# Top.net
KiCad netlist of a schematic drawn in Altium Designer
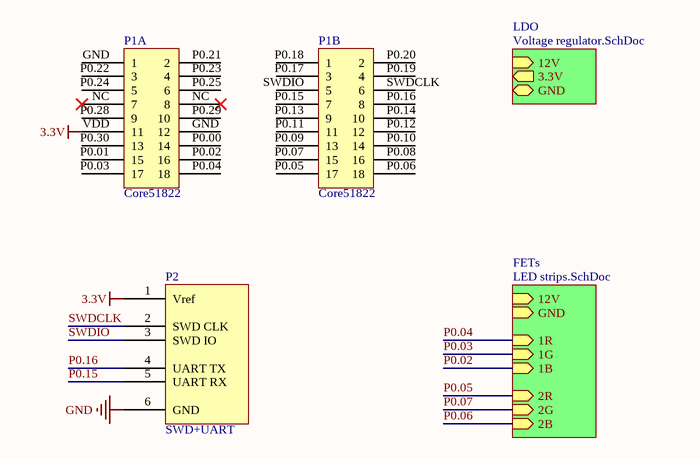
[diagram p0: Top.SchDoc]

(export (version "E")
  (design (tool "Eeschema 10.0.6"))
  (components
    (comp (ref "P1") (value "Core51822") (libsource (lib "Core51822-related") (part "Core51822")))
    (comp (ref "P2") (value "SWD+UART") (libsource (lib "Core51822-related") (part "SWD+UART")))
  )
  (nets
    (net (code "12") (name "/P0.15") (class "Default")
      (node (ref "P2") (pin "5") (pinfunction "UART_RX_5") (pintype "passive"))
    )
    (net (code "13") (name "/P0.16") (class "Default")
      (node (ref "P2") (pin "4") (pinfunction "UART_TX_4") (pintype "passive"))
    )
    (net (code "14") (name "/SWDCLK") (class "Default")
      (node (ref "P2") (pin "2") (pinfunction "SWD_CLK_2") (pintype "passive"))
    )
    (net (code "15") (name "/SWDIO") (class "Default")
      (node (ref "P2") (pin "3") (pinfunction "SWD_IO_3") (pintype "passive"))
    )
    (net (code "16") (name "3.3V") (class "Default")
      (node (ref "P1") (pin "VDD") (pinfunction "11_VDD") (pintype "passive"))
      (node (ref "P2") (pin "1") (pinfunction "Vref_1") (pintype "passive"))
    )
    (net (code "17") (name "GND") (class "Default")
      (node (ref "P2") (pin "6") (pinfunction "GND_6") (pintype "passive"))
    )
    (net (code "18") (name "unconnected-(P1A-1-PadGND)") (class "Default")
      (node (ref "P1") (pin "GND") (pinfunction "1_GND") (pintype "passive"))
    )
    (net (code "19") (name "unconnected-(P1A-2-PadP0.21)") (class "Default")
      (node (ref "P1") (pin "P0.21") (pinfunction "2_P0.21") (pintype "passive"))
    )
    (net (code "20") (name "unconnected-(P1A-3-PadP0.22)") (class "Default")
      (node (ref "P1") (pin "P0.22") (pinfunction "3_P0.22") (pintype "power_in"))
    )
    (net (code "21") (name "unconnected-(P1A-4-PadP0.23)") (class "Default")
      (node (ref "P1") (pin "P0.23") (pinfunction "4_P0.23") (pintype "passive"))
    )
    (net (code "22") (name "unconnected-(P1A-5-PadP0.24)") (class "Default")
      (node (ref "P1") (pin "P0.24") (pinfunction "5_P0.24") (pintype "passive"))
    )
    (net (code "23") (name "unconnected-(P1A-6-PadP0.25)") (class "Default")
      (node (ref "P1") (pin "P0.25") (pinfunction "6_P0.25") (pintype "passive"))
    )
    (net (code "24") (name "unconnected-(P1A-7-PadNC)") (class "Default")
      (node (ref "P1") (pin "NC") (pinfunction "7_NC") (pintype "passive+no_connect"))
    )
    (net (code "25") (name "unconnected-(P1A-8-PadNC)") (class "Default")
      (node (ref "P1") (pin "NC") (pinfunction "8_NC") (pintype "passive+no_connect"))
    )
    (net (code "26") (name "unconnected-(P1A-9-PadP0.28)") (class "Default")
      (node (ref "P1") (pin "P0.28") (pinfunction "9_P0.28") (pintype "passive"))
    )
    (net (code "27") (name "unconnected-(P1A-10-PadP0.29)") (class "Default")
      (node (ref "P1") (pin "P0.29") (pinfunction "10_P0.29") (pintype "passive"))
    )
    (net (code "28") (name "unconnected-(P1A-12-PadGND)") (class "Default")
      (node (ref "P1") (pin "GND") (pinfunction "12_GND") (pintype "passive"))
    )
    (net (code "29") (name "unconnected-(P1A-13-PadP0.30)") (class "Default")
      (node (ref "P1") (pin "P0.30") (pinfunction "13_P0.30") (pintype "passive"))
    )
    (net (code "30") (name "unconnected-(P1A-14-PadP0.00)") (class "Default")
      (node (ref "P1") (pin "P0.00") (pinfunction "14_P0.00") (pintype "passive"))
    )
    (net (code "31") (name "unconnected-(P1A-15-PadP0.01)") (class "Default")
      (node (ref "P1") (pin "P0.01") (pinfunction "15_P0.01") (pintype "passive"))
    )
    (net (code "32") (name "unconnected-(P1A-16-PadP0.02)") (class "Default")
      (node (ref "P1") (pin "P0.02") (pinfunction "16_P0.02") (pintype "passive"))
    )
    (net (code "33") (name "unconnected-(P1A-17-PadP0.03)") (class "Default")
      (node (ref "P1") (pin "P0.03") (pinfunction "17_P0.03") (pintype "passive"))
    )
    (net (code "34") (name "unconnected-(P1A-18-PadP0.04)") (class "Default")
      (node (ref "P1") (pin "P0.04") (pinfunction "18_P0.04") (pintype "passive"))
    )
    (net (code "35") (name "unconnected-(P1B-1-PadP0.18)") (class "Default")
      (node (ref "P1") (pin "P0.18") (pinfunction "1_P0.18") (pintype "passive"))
    )
    (net (code "36") (name "unconnected-(P1B-2-PadP0.20)") (class "Default")
      (node (ref "P1") (pin "P0.20") (pinfunction "2_P0.20") (pintype "passive"))
    )
    (net (code "37") (name "unconnected-(P1B-3-PadP0.17)") (class "Default")
      (node (ref "P1") (pin "P0.17") (pinfunction "3_P0.17") (pintype "power_in"))
    )
    (net (code "38") (name "unconnected-(P1B-4-PadP0.19)") (class "Default")
      (node (ref "P1") (pin "P0.19") (pinfunction "4_P0.19") (pintype "passive"))
    )
    (net (code "39") (name "unconnected-(P1B-5-PadSWDIO)") (class "Default")
      (node (ref "P1") (pin "SWDIO") (pinfunction "5_SWDIO") (pintype "passive"))
    )
    (net (code "40") (name "unconnected-(P1B-6-PadSWDCLK)") (class "Default")
      (node (ref "P1") (pin "SWDCLK") (pinfunction "6_SWDCLK") (pintype "passive"))
    )
    (net (code "41") (name "unconnected-(P1B-7-PadP0.15)") (class "Default")
      (node (ref "P1") (pin "P0.15") (pinfunction "7_P0.15") (pintype "passive"))
    )
    (net (code "42") (name "unconnected-(P1B-8-PadP0.16)") (class "Default")
      (node (ref "P1") (pin "P0.16") (pinfunction "8_P0.16") (pintype "passive"))
    )
    (net (code "43") (name "unconnected-(P1B-9-PadP0.13)") (class "Default")
      (node (ref "P1") (pin "P0.13") (pinfunction "9_P0.13") (pintype "passive"))
    )
    (net (code "44") (name "unconnected-(P1B-10-PadP0.14)") (class "Default")
      (node (ref "P1") (pin "P0.14") (pinfunction "10_P0.14") (pintype "passive"))
    )
    (net (code "45") (name "unconnected-(P1B-11-PadP0.11)") (class "Default")
      (node (ref "P1") (pin "P0.11") (pinfunction "11_P0.11") (pintype "passive"))
    )
    (net (code "46") (name "unconnected-(P1B-12-PadP0.12)") (class "Default")
      (node (ref "P1") (pin "P0.12") (pinfunction "12_P0.12") (pintype "passive"))
    )
    (net (code "47") (name "unconnected-(P1B-13-PadP0.09)") (class "Default")
      (node (ref "P1") (pin "P0.09") (pinfunction "13_P0.09") (pintype "passive"))
    )
    (net (code "48") (name "unconnected-(P1B-14-PadP0.10)") (class "Default")
      (node (ref "P1") (pin "P0.10") (pinfunction "14_P0.10") (pintype "passive"))
    )
    (net (code "49") (name "unconnected-(P1B-15-PadP0.07)") (class "Default")
      (node (ref "P1") (pin "P0.07") (pinfunction "15_P0.07") (pintype "passive"))
    )
    (net (code "50") (name "unconnected-(P1B-16-PadP0.08)") (class "Default")
      (node (ref "P1") (pin "P0.08") (pinfunction "16_P0.08") (pintype "passive"))
    )
    (net (code "51") (name "unconnected-(P1B-17-PadP0.05)") (class "Default")
      (node (ref "P1") (pin "P0.05") (pinfunction "17_P0.05") (pintype "passive"))
    )
    (net (code "52") (name "unconnected-(P1B-18-PadP0.06)") (class "Default")
      (node (ref "P1") (pin "P0.06") (pinfunction "18_P0.06") (pintype "passive"))
    )
  )
)
